# SP8T_ecal_3.net
KiCad netlist of a schematic drawn in Altium Designer
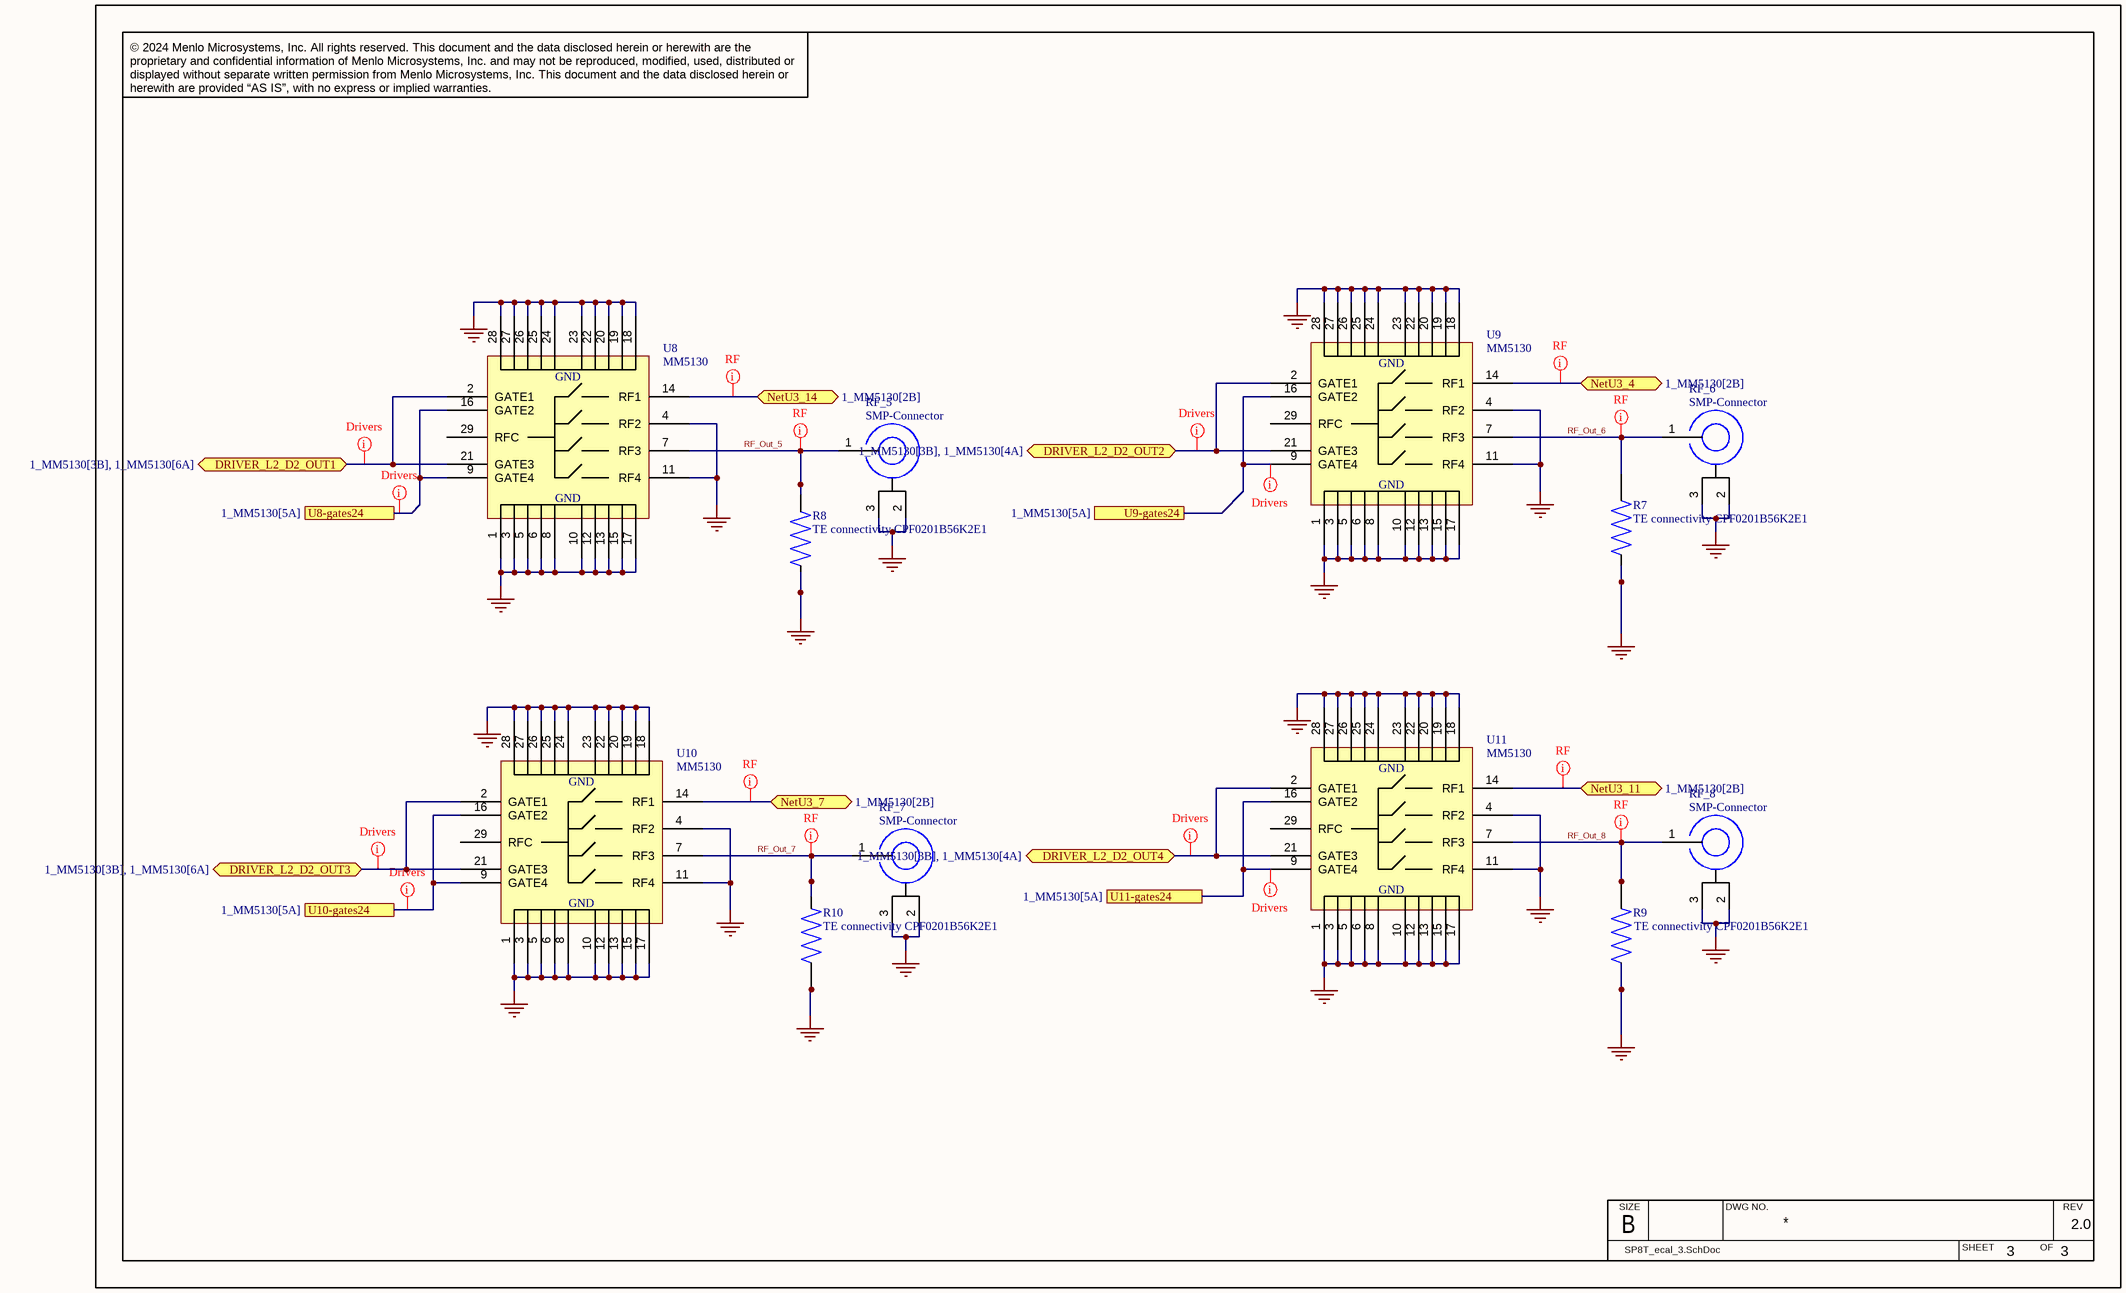
[diagram p0: SP8T_ecal_3.SchDoc]

(export (version "E")
  (design (tool "Eeschema 10.0.6"))
  (components
    (comp (ref "R7")
      (value "TE connectivity CPF0201B56K2E1")
      (footprint "0201-resistor")
      (description "CPF 0201 56K2 0.1% 25PPM 1K RL")
      (fields (field (name "MP") "ERJ1GN0R00C") (field (name "MFGR PART NO.") "CPF0201B56K2E1"))
      (libsource (lib "SchlibLafe") (part "TE connectivity CPF0201B56K2E1"))
    )
    (comp (ref "R8")
      (value "TE connectivity CPF0201B56K2E1")
      (footprint "0201-resistor")
      (description "CPF 0201 56K2 0.1% 25PPM 1K RL")
      (fields (field (name "MP") "ERJ1GN0R00C") (field (name "MFGR PART NO.") "CPF0201B56K2E1"))
      (libsource (lib "SchlibLafe") (part "TE connectivity CPF0201B56K2E1"))
    )
    (comp (ref "R9")
      (value "TE connectivity CPF0201B56K2E1")
      (footprint "0201-resistor")
      (description "CPF 0201 56K2 0.1% 25PPM 1K RL")
      (fields (field (name "MP") "ERJ1GN0R00C") (field (name "MFGR PART NO.") "CPF0201B56K2E1"))
      (libsource (lib "SchlibLafe") (part "TE connectivity CPF0201B56K2E1"))
    )
    (comp (ref "R10")
      (value "TE connectivity CPF0201B56K2E1")
      (footprint "0201-resistor")
      (description "CPF 0201 56K2 0.1% 25PPM 1K RL")
      (fields (field (name "MP") "ERJ1GN0R00C") (field (name "MFGR PART NO.") "CPF0201B56K2E1"))
      (libsource (lib "SchlibLafe") (part "TE connectivity CPF0201B56K2E1"))
    )
    (comp (ref "RF_5")
      (value "PE44490")
      (footprint "CONN-PE44490")
      (description "SMP, Mini Connector Plug, Male Pin 50 Ohms Board Edge, Cutout; Surface Mount Solder")
      (fields (field (name "MANUFACTURER") "Pasternack") (field (name "TYPE") "SMP-Connector"))
      (libsource (lib "Menlo_Altium_Library") (part "CONN-PE44490"))
    )
    (comp (ref "RF_6")
      (value "PE44490")
      (footprint "CONN-PE44490")
      (description "SMP, Mini Connector Plug, Male Pin 50 Ohms Board Edge, Cutout; Surface Mount Solder")
      (fields (field (name "MANUFACTURER") "Pasternack") (field (name "TYPE") "SMP-Connector"))
      (libsource (lib "Menlo_Altium_Library") (part "CONN-PE44490"))
    )
    (comp (ref "RF_7")
      (value "PE44490")
      (footprint "CONN-PE44490")
      (description "SMP, Mini Connector Plug, Male Pin 50 Ohms Board Edge, Cutout; Surface Mount Solder")
      (fields (field (name "MANUFACTURER") "Pasternack") (field (name "TYPE") "SMP-Connector"))
      (libsource (lib "Menlo_Altium_Library") (part "CONN-PE44490"))
    )
    (comp (ref "RF_8")
      (value "PE44490")
      (footprint "CONN-PE44490")
      (description "SMP, Mini Connector Plug, Male Pin 50 Ohms Board Edge, Cutout; Surface Mount Solder")
      (fields (field (name "MANUFACTURER") "Pasternack") (field (name "TYPE") "SMP-Connector"))
      (libsource (lib "Menlo_Altium_Library") (part "CONN-PE44490"))
    )
    (comp (ref "U8")
      (value "MM5130")
      (footprint "MM5130-SP_M_PCB_NOFLOOD")
      (description "High power SP4T MEMs switch")
      (libsource (lib "Menlo_Altium_Library") (part "IC-MM5130"))
    )
    (comp (ref "U9")
      (value "MM5130")
      (footprint "MM5130-SP_M_PCB_NOFLOOD")
      (description "High power SP4T MEMs switch")
      (libsource (lib "Menlo_Altium_Library") (part "IC-MM5130"))
    )
    (comp (ref "U10")
      (value "MM5130")
      (footprint "MM5130-SP_M_PCB_NOFLOOD")
      (description "High power SP4T MEMs switch")
      (libsource (lib "Menlo_Altium_Library") (part "IC-MM5130"))
    )
    (comp (ref "U11")
      (value "MM5130")
      (footprint "MM5130-SP_M_PCB_NOFLOOD")
      (description "High power SP4T MEMs switch")
      (libsource (lib "Menlo_Altium_Library") (part "IC-MM5130"))
    )
  )
  (nets
    (net (code "1") (name "/DRIVER_L2_D2_OUT1") (class "Default")
      (node (ref "U8") (pin "2") (pinfunction "GATE1_2") (pintype "passive"))
      (node (ref "U8") (pin "21") (pinfunction "GATE3_21") (pintype "passive"))
    )
    (net (code "2") (name "/DRIVER_L2_D2_OUT2") (class "Default")
      (node (ref "U9") (pin "2") (pinfunction "GATE1_2") (pintype "passive"))
      (node (ref "U9") (pin "21") (pinfunction "GATE3_21") (pintype "passive"))
    )
    (net (code "3") (name "/DRIVER_L2_D2_OUT3") (class "Default")
      (node (ref "U10") (pin "2") (pinfunction "GATE1_2") (pintype "passive"))
      (node (ref "U10") (pin "21") (pinfunction "GATE3_21") (pintype "passive"))
    )
    (net (code "4") (name "/DRIVER_L2_D2_OUT4") (class "Default")
      (node (ref "U11") (pin "2") (pinfunction "GATE1_2") (pintype "passive"))
      (node (ref "U11") (pin "21") (pinfunction "GATE3_21") (pintype "passive"))
    )
    (net (code "5") (name "/NetU3_4") (class "Default")
      (node (ref "U9") (pin "14") (pinfunction "RF1_14") (pintype "passive"))
    )
    (net (code "6") (name "/NetU3_7") (class "Default")
      (node (ref "U10") (pin "14") (pinfunction "RF1_14") (pintype "passive"))
    )
    (net (code "7") (name "/NetU3_11") (class "Default")
      (node (ref "U11") (pin "14") (pinfunction "RF1_14") (pintype "passive"))
    )
    (net (code "8") (name "/NetU3_14") (class "Default")
      (node (ref "U8") (pin "14") (pinfunction "RF1_14") (pintype "passive"))
    )
    (net (code "9") (name "/RF_Out_5") (class "Default")
      (node (ref "R8") (pin "1") (pinfunction "1_1") (pintype "passive"))
      (node (ref "RF_5") (pin "1") (pinfunction "1_1") (pintype "passive"))
      (node (ref "U8") (pin "7") (pinfunction "RF3_7") (pintype "passive"))
    )
    (net (code "10") (name "/RF_Out_6") (class "Default")
      (node (ref "R7") (pin "1") (pinfunction "1_1") (pintype "passive"))
      (node (ref "RF_6") (pin "1") (pinfunction "1_1") (pintype "passive"))
      (node (ref "U9") (pin "7") (pinfunction "RF3_7") (pintype "passive"))
    )
    (net (code "11") (name "/RF_Out_7") (class "Default")
      (node (ref "R10") (pin "1") (pinfunction "1_1") (pintype "passive"))
      (node (ref "RF_7") (pin "1") (pinfunction "1_1") (pintype "passive"))
      (node (ref "U10") (pin "7") (pinfunction "RF3_7") (pintype "passive"))
    )
    (net (code "12") (name "/RF_Out_8") (class "Default")
      (node (ref "R9") (pin "1") (pinfunction "1_1") (pintype "passive"))
      (node (ref "RF_8") (pin "1") (pinfunction "1_1") (pintype "passive"))
      (node (ref "U11") (pin "7") (pinfunction "RF3_7") (pintype "passive"))
    )
    (net (code "13") (name "/U8-gates24") (class "Default")
      (node (ref "U8") (pin "16") (pinfunction "GATE2_16") (pintype "passive"))
      (node (ref "U8") (pin "9") (pinfunction "GATE4_9") (pintype "passive"))
    )
    (net (code "14") (name "/U9-gates24") (class "Default")
      (node (ref "U9") (pin "16") (pinfunction "GATE2_16") (pintype "passive"))
      (node (ref "U9") (pin "9") (pinfunction "GATE4_9") (pintype "passive"))
    )
    (net (code "15") (name "/U10-gates24") (class "Default")
      (node (ref "U10") (pin "16") (pinfunction "GATE2_16") (pintype "passive"))
      (node (ref "U10") (pin "9") (pinfunction "GATE4_9") (pintype "passive"))
    )
    (net (code "16") (name "/U11-gates24") (class "Default")
      (node (ref "U11") (pin "16") (pinfunction "GATE2_16") (pintype "passive"))
      (node (ref "U11") (pin "9") (pinfunction "GATE4_9") (pintype "passive"))
    )
    (net (code "17") (name "GND") (class "Default")
      (node (ref "R10") (pin "2") (pinfunction "2_2") (pintype "passive"))
      (node (ref "R7") (pin "2") (pinfunction "2_2") (pintype "passive"))
      (node (ref "R8") (pin "2") (pinfunction "2_2") (pintype "passive"))
      (node (ref "R9") (pin "2") (pinfunction "2_2") (pintype "passive"))
      (node (ref "RF_5") (pin "2") (pinfunction "2_2") (pintype "passive"))
      (node (ref "RF_5") (pin "3") (pinfunction "3_3") (pintype "passive"))
      (node (ref "RF_6") (pin "2") (pinfunction "2_2") (pintype "passive"))
      (node (ref "RF_6") (pin "3") (pinfunction "3_3") (pintype "passive"))
      (node (ref "RF_7") (pin "2") (pinfunction "2_2") (pintype "passive"))
      (node (ref "RF_7") (pin "3") (pinfunction "3_3") (pintype "passive"))
      (node (ref "RF_8") (pin "2") (pinfunction "2_2") (pintype "passive"))
      (node (ref "RF_8") (pin "3") (pinfunction "3_3") (pintype "passive"))
      (node (ref "U10") (pin "1") (pinfunction "GND_1") (pintype "passive"))
      (node (ref "U10") (pin "10") (pinfunction "GND_10") (pintype "passive"))
      (node (ref "U10") (pin "11") (pinfunction "RF4_11") (pintype "passive"))
      (node (ref "U10") (pin "12") (pinfunction "GND_12") (pintype "passive"))
      (node (ref "U10") (pin "13") (pinfunction "GND_13") (pintype "passive"))
      (node (ref "U10") (pin "15") (pinfunction "GND_15") (pintype "passive"))
      (node (ref "U10") (pin "17") (pinfunction "GND_17") (pintype "passive"))
      (node (ref "U10") (pin "18") (pinfunction "GND_18") (pintype "passive"))
      (node (ref "U10") (pin "19") (pinfunction "GND_19") (pintype "passive"))
      (node (ref "U10") (pin "20") (pinfunction "GND_20") (pintype "passive"))
      (node (ref "U10") (pin "22") (pinfunction "GND_22") (pintype "passive"))
      (node (ref "U10") (pin "23") (pinfunction "GND_23") (pintype "passive"))
      (node (ref "U10") (pin "24") (pinfunction "GND_24") (pintype "passive"))
      (node (ref "U10") (pin "25") (pinfunction "GND_25") (pintype "passive"))
      (node (ref "U10") (pin "26") (pinfunction "GND_26") (pintype "passive"))
      (node (ref "U10") (pin "27") (pinfunction "GND_27") (pintype "passive"))
      (node (ref "U10") (pin "28") (pinfunction "GND_28") (pintype "passive"))
      (node (ref "U10") (pin "3") (pinfunction "GND_3") (pintype "passive"))
      (node (ref "U10") (pin "4") (pinfunction "RF2_4") (pintype "passive"))
      (node (ref "U10") (pin "5") (pinfunction "GND_5") (pintype "passive"))
      (node (ref "U10") (pin "6") (pinfunction "GND_6") (pintype "passive"))
      (node (ref "U10") (pin "8") (pinfunction "GND_8") (pintype "passive"))
      (node (ref "U11") (pin "1") (pinfunction "GND_1") (pintype "passive"))
      (node (ref "U11") (pin "10") (pinfunction "GND_10") (pintype "passive"))
      (node (ref "U11") (pin "11") (pinfunction "RF4_11") (pintype "passive"))
      (node (ref "U11") (pin "12") (pinfunction "GND_12") (pintype "passive"))
      (node (ref "U11") (pin "13") (pinfunction "GND_13") (pintype "passive"))
      (node (ref "U11") (pin "15") (pinfunction "GND_15") (pintype "passive"))
      (node (ref "U11") (pin "17") (pinfunction "GND_17") (pintype "passive"))
      (node (ref "U11") (pin "18") (pinfunction "GND_18") (pintype "passive"))
      (node (ref "U11") (pin "19") (pinfunction "GND_19") (pintype "passive"))
      (node (ref "U11") (pin "20") (pinfunction "GND_20") (pintype "passive"))
      (node (ref "U11") (pin "22") (pinfunction "GND_22") (pintype "passive"))
      (node (ref "U11") (pin "23") (pinfunction "GND_23") (pintype "passive"))
      (node (ref "U11") (pin "24") (pinfunction "GND_24") (pintype "passive"))
      (node (ref "U11") (pin "25") (pinfunction "GND_25") (pintype "passive"))
      (node (ref "U11") (pin "26") (pinfunction "GND_26") (pintype "passive"))
      (node (ref "U11") (pin "27") (pinfunction "GND_27") (pintype "passive"))
      (node (ref "U11") (pin "28") (pinfunction "GND_28") (pintype "passive"))
      (node (ref "U11") (pin "3") (pinfunction "GND_3") (pintype "passive"))
      (node (ref "U11") (pin "4") (pinfunction "RF2_4") (pintype "passive"))
      (node (ref "U11") (pin "5") (pinfunction "GND_5") (pintype "passive"))
      (node (ref "U11") (pin "6") (pinfunction "GND_6") (pintype "passive"))
      (node (ref "U11") (pin "8") (pinfunction "GND_8") (pintype "passive"))
      (node (ref "U8") (pin "1") (pinfunction "GND_1") (pintype "passive"))
      (node (ref "U8") (pin "10") (pinfunction "GND_10") (pintype "passive"))
      (node (ref "U8") (pin "11") (pinfunction "RF4_11") (pintype "passive"))
      (node (ref "U8") (pin "12") (pinfunction "GND_12") (pintype "passive"))
      (node (ref "U8") (pin "13") (pinfunction "GND_13") (pintype "passive"))
      (node (ref "U8") (pin "15") (pinfunction "GND_15") (pintype "passive"))
      (node (ref "U8") (pin "17") (pinfunction "GND_17") (pintype "passive"))
      (node (ref "U8") (pin "18") (pinfunction "GND_18") (pintype "passive"))
      (node (ref "U8") (pin "19") (pinfunction "GND_19") (pintype "passive"))
      (node (ref "U8") (pin "20") (pinfunction "GND_20") (pintype "passive"))
      (node (ref "U8") (pin "22") (pinfunction "GND_22") (pintype "passive"))
      (node (ref "U8") (pin "23") (pinfunction "GND_23") (pintype "passive"))
      (node (ref "U8") (pin "24") (pinfunction "GND_24") (pintype "passive"))
      (node (ref "U8") (pin "25") (pinfunction "GND_25") (pintype "passive"))
      (node (ref "U8") (pin "26") (pinfunction "GND_26") (pintype "passive"))
      (node (ref "U8") (pin "27") (pinfunction "GND_27") (pintype "passive"))
      (node (ref "U8") (pin "28") (pinfunction "GND_28") (pintype "passive"))
      (node (ref "U8") (pin "3") (pinfunction "GND_3") (pintype "passive"))
      (node (ref "U8") (pin "4") (pinfunction "RF2_4") (pintype "passive"))
      (node (ref "U8") (pin "5") (pinfunction "GND_5") (pintype "passive"))
      (node (ref "U8") (pin "6") (pinfunction "GND_6") (pintype "passive"))
      (node (ref "U8") (pin "8") (pinfunction "GND_8") (pintype "passive"))
      (node (ref "U9") (pin "1") (pinfunction "GND_1") (pintype "passive"))
      (node (ref "U9") (pin "10") (pinfunction "GND_10") (pintype "passive"))
      (node (ref "U9") (pin "11") (pinfunction "RF4_11") (pintype "passive"))
      (node (ref "U9") (pin "12") (pinfunction "GND_12") (pintype "passive"))
      (node (ref "U9") (pin "13") (pinfunction "GND_13") (pintype "passive"))
      (node (ref "U9") (pin "15") (pinfunction "GND_15") (pintype "passive"))
      (node (ref "U9") (pin "17") (pinfunction "GND_17") (pintype "passive"))
      (node (ref "U9") (pin "18") (pinfunction "GND_18") (pintype "passive"))
      (node (ref "U9") (pin "19") (pinfunction "GND_19") (pintype "passive"))
      (node (ref "U9") (pin "20") (pinfunction "GND_20") (pintype "passive"))
      (node (ref "U9") (pin "22") (pinfunction "GND_22") (pintype "passive"))
      (node (ref "U9") (pin "23") (pinfunction "GND_23") (pintype "passive"))
      (node (ref "U9") (pin "24") (pinfunction "GND_24") (pintype "passive"))
      (node (ref "U9") (pin "25") (pinfunction "GND_25") (pintype "passive"))
      (node (ref "U9") (pin "26") (pinfunction "GND_26") (pintype "passive"))
      (node (ref "U9") (pin "27") (pinfunction "GND_27") (pintype "passive"))
      (node (ref "U9") (pin "28") (pinfunction "GND_28") (pintype "passive"))
      (node (ref "U9") (pin "3") (pinfunction "GND_3") (pintype "passive"))
      (node (ref "U9") (pin "4") (pinfunction "RF2_4") (pintype "passive"))
      (node (ref "U9") (pin "5") (pinfunction "GND_5") (pintype "passive"))
      (node (ref "U9") (pin "6") (pinfunction "GND_6") (pintype "passive"))
      (node (ref "U9") (pin "8") (pinfunction "GND_8") (pintype "passive"))
    )
    (net (code "18") (name "unconnected-(U8-RFC-Pad29)") (class "Default")
      (node (ref "U8") (pin "29") (pinfunction "RFC_29") (pintype "passive"))
    )
    (net (code "19") (name "unconnected-(U9-RFC-Pad29)") (class "Default")
      (node (ref "U9") (pin "29") (pinfunction "RFC_29") (pintype "passive"))
    )
    (net (code "20") (name "unconnected-(U10-RFC-Pad29)") (class "Default")
      (node (ref "U10") (pin "29") (pinfunction "RFC_29") (pintype "passive"))
    )
    (net (code "21") (name "unconnected-(U11-RFC-Pad29)") (class "Default")
      (node (ref "U11") (pin "29") (pinfunction "RFC_29") (pintype "passive"))
    )
  )
)
